# Sheet1_test.net
KiCad netlist of a schematic drawn in Altium Designer
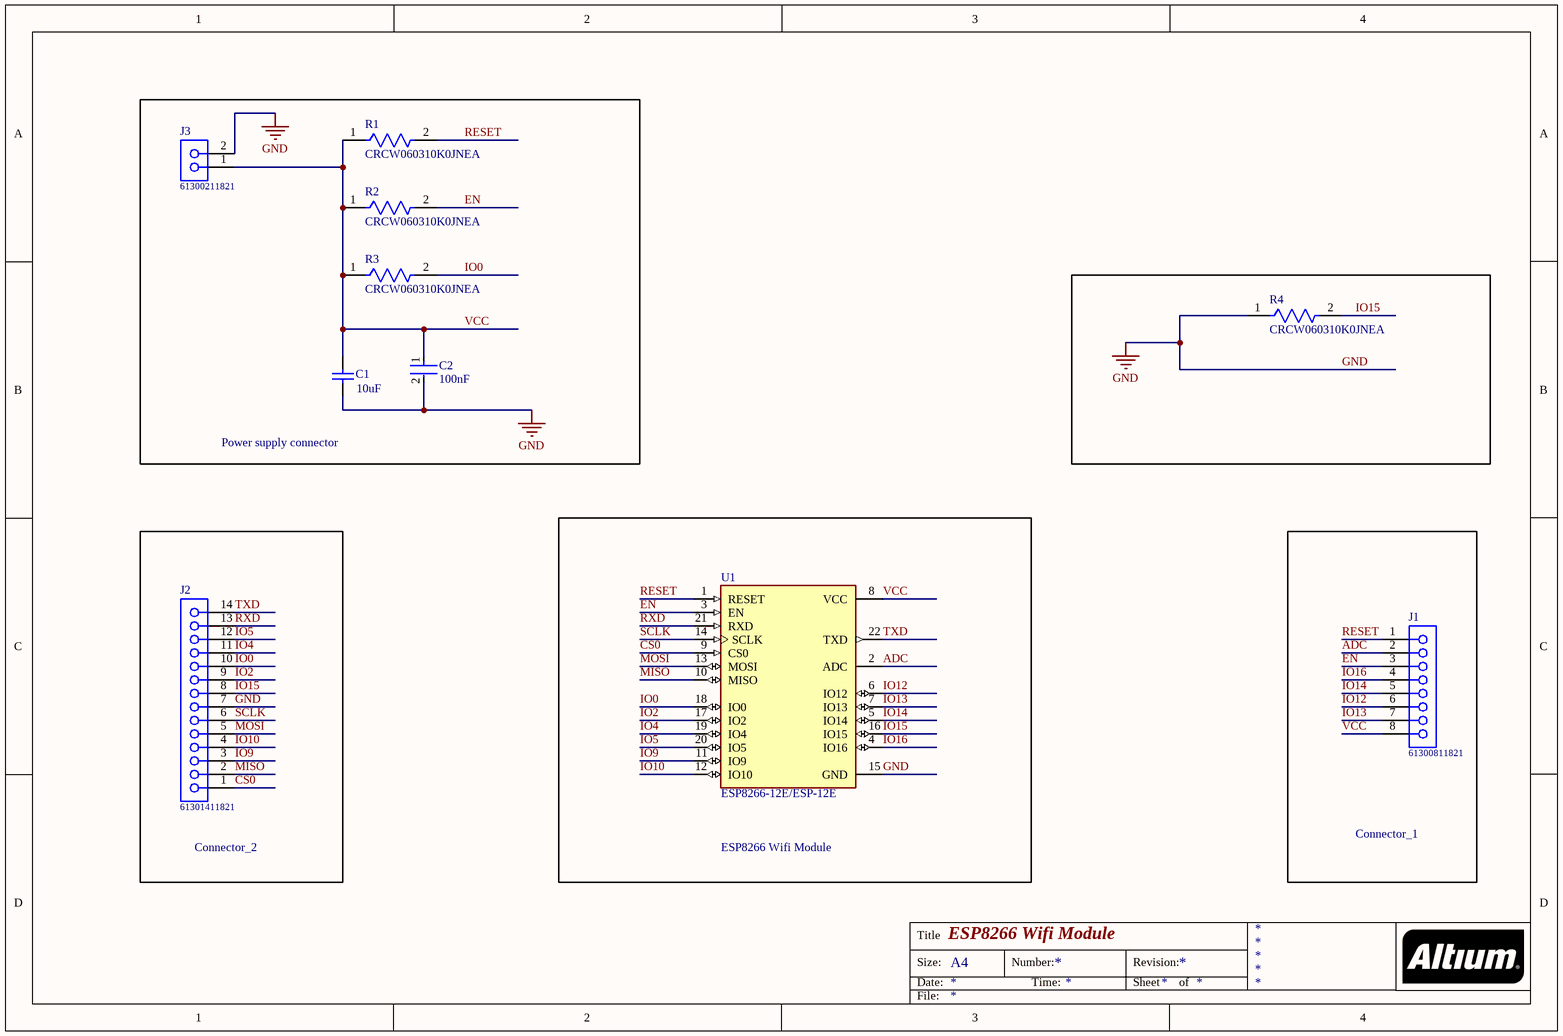
[diagram p0: Sheet1(test).SchDoc]

(export (version "E")
  (design (tool "Eeschema 10.0.6"))
  (components
    (comp (ref "C1")
      (value "10uF")
      (footprint "CAPC2013X95X45ML10T25")
      (fields (field (name "MANUFACTURER") "Murata") (field (name "PART NUMBER") "GRM219R61E106KA12D"))
      (libsource (lib "Altium Content Vault") (part "CAP"))
    )
    (comp (ref "C2")
      (value "100nF")
      (footprint "FP-CL43-IPC_B")
      (description "Cap Ceramic 100nF 500V X7R ±10% SMD 1812 +125°C Embossed T/R")
      (fields (field (name "VOLTAGE") "500V") (field (name "TOLERANCE") "10%"))
      (libsource (lib "Altium Content Vault") (part "b4654b650e69147ec39a6b967a45e02"))
    )
    (comp (ref "J1")
      (value "61300811821")
      (footprint "61300811821")
      (description "WR-PHD Socket Header, THT, pitch 2.54mm, Single Row, Vertical, 8p")
      (fields (field (name "MANUFACTURER") "Wurth Elektronik"))
      (libsource (lib "Altium_WR-PHD (rev20a)") (part "61300811821"))
    )
    (comp (ref "J2")
      (value "61301411821")
      (footprint "61301411821")
      (description "WR-PHD Socket Header, THT, pitch 2.54mm, Single Row, Vertical, 14p")
      (fields (field (name "MANUFACTURER") "Wurth Elektronik"))
      (libsource (lib "Altium_WR-PHD (rev20a) (2)") (part "61301411821"))
    )
    (comp (ref "J3")
      (value "61300211821")
      (footprint "61300211821")
      (description "WR-PHD Socket Header, THT, pitch 2.54mm, Single Row, Vertical, 2p")
      (fields (field (name "MANUFACTURER") "Wurth Elektronik"))
      (libsource (lib "Altium_WR-PHD (rev20a) (3)") (part "61300211821"))
    )
    (comp (ref "R1")
      (value "CRCW060310K0JNEA")
      (footprint "FP-CRCW0603-e3-MFG")
      (description "RES Thick Film, 10kΩ, 5%, 0.1W, 200ppm/°C, 0603")
      (fields (field (name "TOLERANCE") "5%"))
      (libsource (lib "Altium Content Vault") (part "1029c3af85768c4190bb7ad29bc67b5"))
    )
    (comp (ref "R2")
      (value "CRCW060310K0JNEA")
      (footprint "FP-CRCW0603-e3-MFG")
      (description "RES Thick Film, 10kΩ, 5%, 0.1W, 200ppm/°C, 0603")
      (fields (field (name "TOLERANCE") "5%"))
      (libsource (lib "Altium Content Vault") (part "1029c3af85768c4190bb7ad29bc67b5"))
    )
    (comp (ref "R3")
      (value "CRCW060310K0JNEA")
      (footprint "FP-CRCW0603-e3-MFG")
      (description "RES Thick Film, 10kΩ, 5%, 0.1W, 200ppm/°C, 0603")
      (fields (field (name "TOLERANCE") "5%"))
      (libsource (lib "Altium Content Vault") (part "1029c3af85768c4190bb7ad29bc67b5"))
    )
    (comp (ref "R4")
      (value "CRCW060310K0JNEA")
      (footprint "FP-CRCW0603-e3-MFG")
      (description "RES Thick Film, 10kΩ, 5%, 0.1W, 200ppm/°C, 0603")
      (fields (field (name "TOLERANCE") "5%"))
      (libsource (lib "Altium Content Vault") (part "1029c3af85768c4190bb7ad29bc67b5"))
    )
    (comp (ref "U1")
      (value "ESP8266-12E/ESP-12E")
      (footprint "XCVR_ESP8266-12E/ESP-12E")
      (fields (field (name "MF") "AI-Thinker"))
      (libsource (lib "ESP8266-12E_ESP-12E") (part "ESP8266-12E/ESP-12E"))
    )
  )
  (nets
    (net (code "1") (name "/ADC") (class "Default")
      (node (ref "J1") (pin "2") (pinfunction "2_2") (pintype "passive"))
      (node (ref "U1") (pin "2") (pinfunction "ADC_2") (pintype "passive"))
    )
    (net (code "2") (name "/CS0") (class "Default")
      (node (ref "J2") (pin "1") (pinfunction "1_1") (pintype "passive"))
      (node (ref "U1") (pin "9") (pinfunction "CS0_9") (pintype "input"))
    )
    (net (code "3") (name "/EN") (class "Default")
      (node (ref "J1") (pin "3") (pinfunction "3_3") (pintype "passive"))
      (node (ref "R2") (pin "2") (pinfunction "2_2") (pintype "passive"))
      (node (ref "U1") (pin "3") (pinfunction "EN_3") (pintype "input"))
    )
    (net (code "4") (name "/IO0") (class "Default")
      (node (ref "J2") (pin "10") (pinfunction "10_10") (pintype "passive"))
      (node (ref "R3") (pin "2") (pinfunction "2_2") (pintype "passive"))
      (node (ref "U1") (pin "18") (pinfunction "IO0_18") (pintype "bidirectional"))
    )
    (net (code "5") (name "/IO2") (class "Default")
      (node (ref "J2") (pin "9") (pinfunction "9_9") (pintype "passive"))
      (node (ref "U1") (pin "17") (pinfunction "IO2_17") (pintype "bidirectional"))
    )
    (net (code "6") (name "/IO4") (class "Default")
      (node (ref "J2") (pin "11") (pinfunction "11_11") (pintype "passive"))
      (node (ref "U1") (pin "19") (pinfunction "IO4_19") (pintype "bidirectional"))
    )
    (net (code "7") (name "/IO5") (class "Default")
      (node (ref "J2") (pin "12") (pinfunction "12_12") (pintype "passive"))
      (node (ref "U1") (pin "20") (pinfunction "IO5_20") (pintype "bidirectional"))
    )
    (net (code "8") (name "/IO9") (class "Default")
      (node (ref "J2") (pin "3") (pinfunction "3_3") (pintype "passive"))
      (node (ref "U1") (pin "11") (pinfunction "IO9_11") (pintype "bidirectional"))
    )
    (net (code "9") (name "/IO10") (class "Default")
      (node (ref "J2") (pin "4") (pinfunction "4_4") (pintype "passive"))
      (node (ref "U1") (pin "12") (pinfunction "IO10_12") (pintype "bidirectional"))
    )
    (net (code "10") (name "/IO12") (class "Default")
      (node (ref "J1") (pin "6") (pinfunction "6_6") (pintype "passive"))
      (node (ref "U1") (pin "6") (pinfunction "IO12_6") (pintype "bidirectional"))
    )
    (net (code "11") (name "/IO13") (class "Default")
      (node (ref "J1") (pin "7") (pinfunction "7_7") (pintype "passive"))
      (node (ref "U1") (pin "7") (pinfunction "IO13_7") (pintype "bidirectional"))
    )
    (net (code "12") (name "/IO14") (class "Default")
      (node (ref "J1") (pin "5") (pinfunction "5_5") (pintype "passive"))
      (node (ref "U1") (pin "5") (pinfunction "IO14_5") (pintype "bidirectional"))
    )
    (net (code "13") (name "/IO15") (class "Default")
      (node (ref "J2") (pin "8") (pinfunction "8_8") (pintype "passive"))
      (node (ref "R4") (pin "2") (pinfunction "2_2") (pintype "passive"))
      (node (ref "U1") (pin "16") (pinfunction "IO15_16") (pintype "bidirectional"))
    )
    (net (code "14") (name "/IO16") (class "Default")
      (node (ref "J1") (pin "4") (pinfunction "4_4") (pintype "passive"))
      (node (ref "U1") (pin "4") (pinfunction "IO16_4") (pintype "bidirectional"))
    )
    (net (code "15") (name "/MISO") (class "Default")
      (node (ref "J2") (pin "2") (pinfunction "2_2") (pintype "passive"))
      (node (ref "U1") (pin "10") (pinfunction "MISO_10") (pintype "bidirectional"))
    )
    (net (code "16") (name "/MOSI") (class "Default")
      (node (ref "J2") (pin "5") (pinfunction "5_5") (pintype "passive"))
      (node (ref "U1") (pin "13") (pinfunction "MOSI_13") (pintype "bidirectional"))
    )
    (net (code "17") (name "/RESET") (class "Default")
      (node (ref "J1") (pin "1") (pinfunction "1_1") (pintype "passive"))
      (node (ref "R1") (pin "2") (pinfunction "2_2") (pintype "passive"))
      (node (ref "U1") (pin "1") (pinfunction "RESET_1") (pintype "input"))
    )
    (net (code "18") (name "/RXD") (class "Default")
      (node (ref "J2") (pin "13") (pinfunction "13_13") (pintype "passive"))
      (node (ref "U1") (pin "21") (pinfunction "RXD_21") (pintype "input"))
    )
    (net (code "19") (name "/SCLK") (class "Default")
      (node (ref "J2") (pin "6") (pinfunction "6_6") (pintype "passive"))
      (node (ref "U1") (pin "14") (pinfunction "SCLK_14") (pintype "input"))
    )
    (net (code "20") (name "/TXD") (class "Default")
      (node (ref "J2") (pin "14") (pinfunction "14_14") (pintype "passive"))
      (node (ref "U1") (pin "22") (pinfunction "TXD_22") (pintype "output"))
    )
    (net (code "21") (name "/VCC") (class "Default")
      (node (ref "C1") (pin "2") (pinfunction "2_2") (pintype "passive"))
      (node (ref "C2") (pin "1") (pinfunction "1_1") (pintype "passive"))
      (node (ref "J1") (pin "8") (pinfunction "8_8") (pintype "passive"))
      (node (ref "J3") (pin "1") (pinfunction "1_1") (pintype "passive"))
      (node (ref "R1") (pin "1") (pinfunction "1_1") (pintype "passive"))
      (node (ref "R2") (pin "1") (pinfunction "1_1") (pintype "passive"))
      (node (ref "R3") (pin "1") (pinfunction "1_1") (pintype "passive"))
      (node (ref "U1") (pin "8") (pinfunction "VCC_8") (pintype "power_in"))
    )
    (net (code "22") (name "GND") (class "Default")
      (node (ref "C1") (pin "1") (pinfunction "1_1") (pintype "passive"))
      (node (ref "C2") (pin "2") (pinfunction "2_2") (pintype "passive"))
      (node (ref "J2") (pin "7") (pinfunction "7_7") (pintype "passive"))
      (node (ref "J3") (pin "2") (pinfunction "2_2") (pintype "passive"))
      (node (ref "R4") (pin "1") (pinfunction "1_1") (pintype "passive"))
      (node (ref "U1") (pin "15") (pinfunction "GND_15") (pintype "power_in"))
    )
  )
)
